# SCH_uCompute_Robot_2026-03-14.net
KiCad netlist of a schematic drawn in EasyEDA
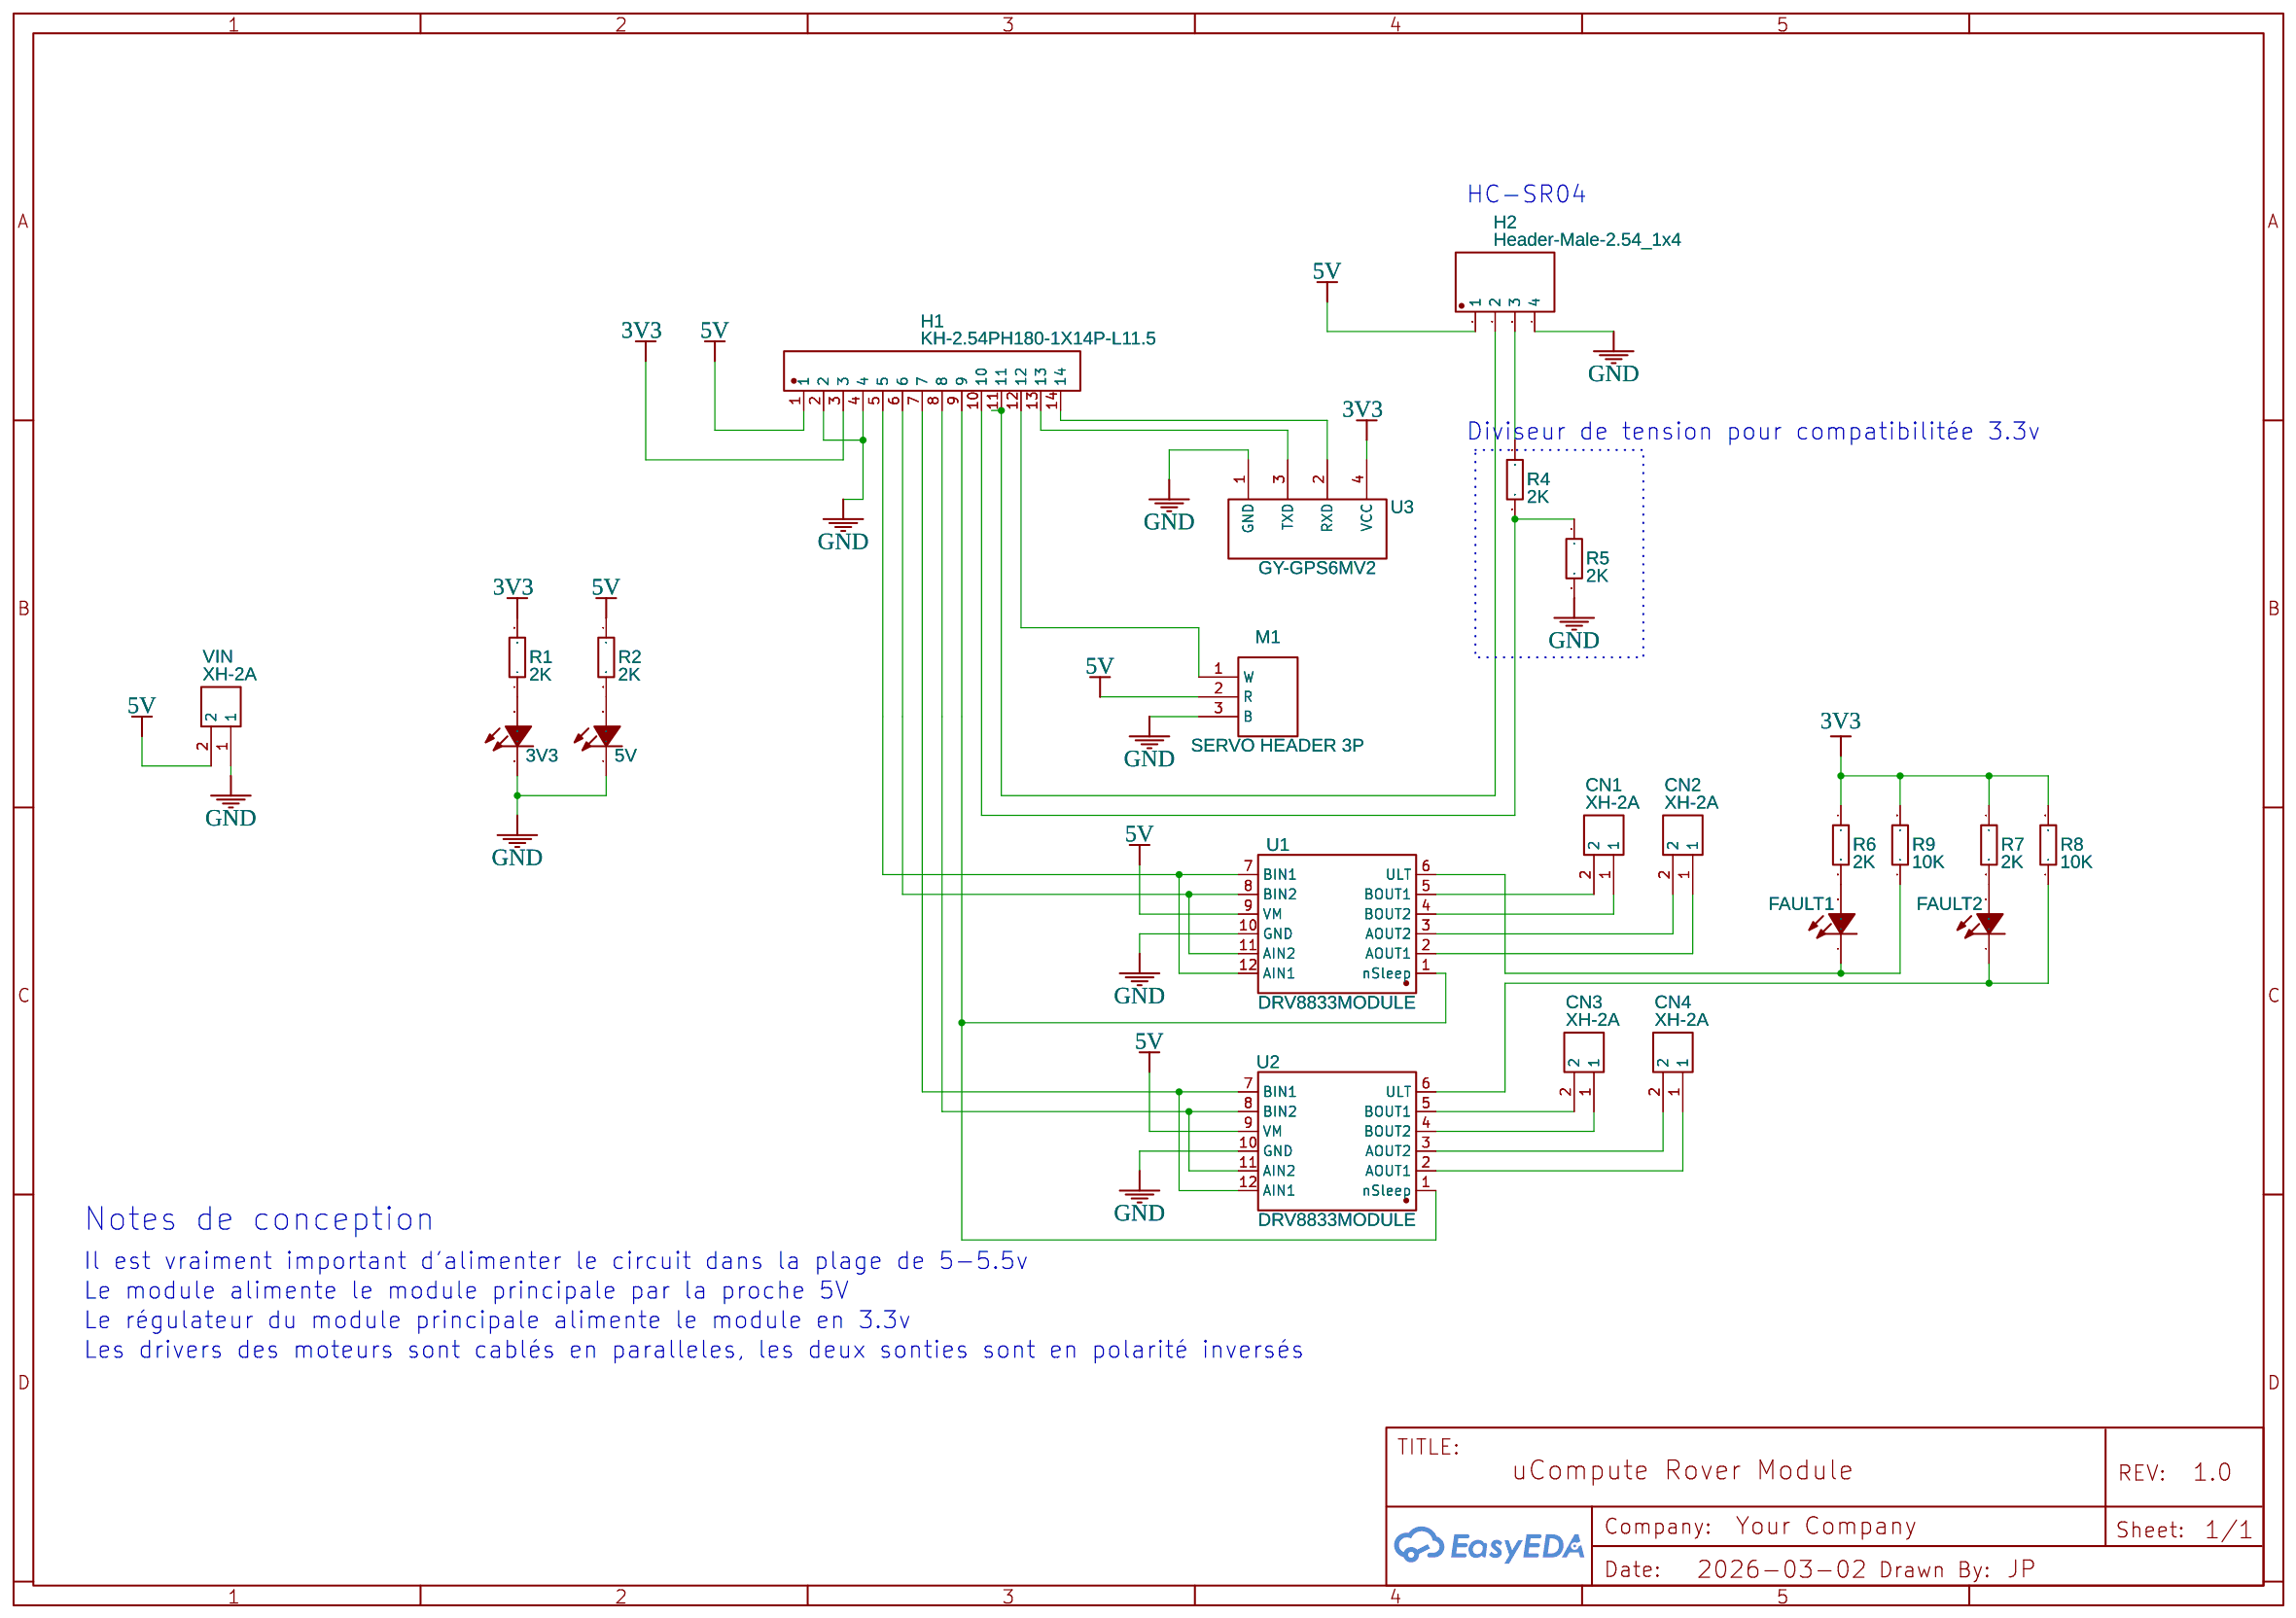
[diagram p0: schematic sheet]

(export (version "E")
  (design (tool "Eeschema 10.0.6"))
  (components
    (comp (ref "3V3")
      (value "XL-1206QPC")
      (fields (field (name "Manufacturer") "LCSC"))
      (libsource (lib "") (part "XL-1206QPC_1"))
    )
    (comp (ref "5V")
      (value "XL-1206QPC")
      (fields (field (name "Manufacturer") "LCSC"))
      (libsource (lib "") (part "XL-1206QPC_2"))
    )
    (comp (ref "CN1")
      (value "XH-2A")
      (fields (field (name "Manufacturer") "BOOMELE(博穆精密)"))
      (libsource (lib "") (part "XH-2A_1"))
    )
    (comp (ref "CN2")
      (value "XH-2A")
      (fields (field (name "Manufacturer") "BOOMELE(博穆精密)"))
      (libsource (lib "") (part "XH-2A_1"))
    )
    (comp (ref "CN3")
      (value "XH-2A")
      (fields (field (name "Manufacturer") "BOOMELE(博穆精密)"))
      (libsource (lib "") (part "XH-2A_1"))
    )
    (comp (ref "CN4")
      (value "XH-2A")
      (fields (field (name "Manufacturer") "BOOMELE(博穆精密)"))
      (libsource (lib "") (part "XH-2A_1"))
    )
    (comp (ref "FAULT1")
      (value "XL-1206QPC")
      (fields (field (name "Manufacturer") "LCSC"))
      (libsource (lib "") (part "XL-1206QPC"))
    )
    (comp (ref "FAULT2")
      (value "XL-1206QPC")
      (fields (field (name "Manufacturer") "LCSC"))
      (libsource (lib "") (part "XL-1206QPC"))
    )
    (comp (ref "H1")
      (value "KH-2.54PH180-1X14P-L11.5")
      (fields (field (name "Manufacturer") "kinghelm(金航标)"))
      (libsource (lib "") (part "KH-2.54PH180-1X14P-L11.5"))
    )
    (comp (ref "H2")
      (value "Header-Male-2.54_1x4")
      (fields (field (name "Manufacturer Part") "B-2100S04P-A110") (field (name "Manufacturer") "Ckmtw(灿科盟)"))
      (libsource (lib "") (part "Header-Male-2.54_1x4"))
    )
    (comp (ref "M1")
      (value "SERVO HEADER 3P")
      (fields (field (name "Manufacturer Part") "New SchematicLib"))
      (libsource (lib "") (part "SERVO HEADER 3P"))
    )
    (comp (ref "R1")
      (value "2K")
      (fields (field (name "Manufacturer Part") "RC0805DR-071KL") (field (name "Manufacturer") "YAGEO(国巨)"))
      (libsource (lib "") (part "RC0805DR-071KL_1"))
    )
    (comp (ref "R2")
      (value "2K")
      (fields (field (name "Manufacturer Part") "RC0805DR-071KL") (field (name "Manufacturer") "YAGEO(国巨)"))
      (libsource (lib "") (part "RC0805DR-071KL"))
    )
    (comp (ref "R4")
      (value "2K")
      (fields (field (name "Manufacturer Part") "RC0805DR-071KL") (field (name "Manufacturer") "YAGEO(国巨)"))
      (libsource (lib "") (part "RC0805DR-071KL"))
    )
    (comp (ref "R5")
      (value "2K")
      (fields (field (name "Manufacturer Part") "RC0805DR-071KL") (field (name "Manufacturer") "YAGEO(国巨)"))
      (libsource (lib "") (part "RC0805DR-071KL"))
    )
    (comp (ref "R6")
      (value "2K")
      (fields (field (name "Manufacturer Part") "RC0805DR-071KL") (field (name "Manufacturer") "YAGEO(国巨)"))
      (libsource (lib "") (part "RC0805DR-071KL"))
    )
    (comp (ref "R7")
      (value "2K")
      (fields (field (name "Manufacturer Part") "RC0805DR-071KL") (field (name "Manufacturer") "YAGEO(国巨)"))
      (libsource (lib "") (part "RC0805DR-071KL"))
    )
    (comp (ref "R8")
      (value "10K")
      (fields (field (name "Manufacturer Part") "RC0805DR-071KL") (field (name "Manufacturer") "YAGEO(国巨)"))
      (libsource (lib "") (part "RC0805DR-071KL_1"))
    )
    (comp (ref "R9")
      (value "10K")
      (fields (field (name "Manufacturer Part") "RC0805DR-071KL") (field (name "Manufacturer") "YAGEO(国巨)"))
      (libsource (lib "") (part "RC0805DR-071KL_1"))
    )
    (comp (ref "U1")
      (value "DRV8833MODULE")
      (fields (field (name "Manufacturer Part") "DRV8833PWR") (field (name "Manufacturer") "TI(德州仪器)"))
      (libsource (lib "") (part "DRV8833MODULE"))
    )
    (comp (ref "U2")
      (value "DRV8833MODULE")
      (fields (field (name "Manufacturer Part") "DRV8833PWR") (field (name "Manufacturer") "TI(德州仪器)"))
      (libsource (lib "") (part "DRV8833MODULE"))
    )
    (comp (ref "U3") (value "GY-GPS6MV2") (libsource (lib "") (part "GY-GPS6MV2")))
    (comp (ref "VIN")
      (value "XH-2A")
      (fields (field (name "Manufacturer") "BOOMELE(博穆精密)"))
      (libsource (lib "") (part "XH-2A"))
    )
  )
  (nets
    (net (code "1") (name "3V3") (class "Default")
      (node (ref "H1") (pin "3") (pinfunction "3_3") (pintype "unspecified"))
      (node (ref "R1") (pin "2") (pinfunction "2_2") (pintype "unspecified"))
      (node (ref "R6") (pin "1") (pinfunction "1_1") (pintype "unspecified"))
      (node (ref "R7") (pin "1") (pinfunction "1_1") (pintype "unspecified"))
      (node (ref "R8") (pin "2") (pinfunction "2_2") (pintype "unspecified"))
      (node (ref "R9") (pin "2") (pinfunction "2_2") (pintype "unspecified"))
      (node (ref "U3") (pin "4") (pinfunction "VCC_4") (pintype "bidirectional"))
    )
    (net (code "2") (name "5V") (class "Default")
      (node (ref "H1") (pin "1") (pinfunction "1_1") (pintype "unspecified"))
      (node (ref "H2") (pin "1") (pinfunction "1_1") (pintype "unspecified"))
      (node (ref "M1") (pin "2") (pinfunction "R_2") (pintype "unspecified"))
      (node (ref "R2") (pin "1") (pinfunction "1_1") (pintype "unspecified"))
      (node (ref "U1") (pin "9") (pinfunction "VM_9") (pintype "unspecified"))
      (node (ref "U2") (pin "9") (pinfunction "VM_9") (pintype "unspecified"))
      (node (ref "VIN") (pin "2") (pinfunction "2_2") (pintype "unspecified"))
    )
    (net (code "3") (name "GND") (class "Default")
      (node (ref "3V3") (pin "1") (pinfunction "K_1") (pintype "unspecified"))
      (node (ref "5V") (pin "1") (pinfunction "K_1") (pintype "unspecified"))
      (node (ref "H1") (pin "2") (pinfunction "2_2") (pintype "unspecified"))
      (node (ref "H1") (pin "4") (pinfunction "4_4") (pintype "unspecified"))
      (node (ref "H2") (pin "4") (pinfunction "4_4") (pintype "unspecified"))
      (node (ref "M1") (pin "3") (pinfunction "B_3") (pintype "unspecified"))
      (node (ref "R5") (pin "2") (pinfunction "2_2") (pintype "unspecified"))
      (node (ref "U1") (pin "10") (pinfunction "GND_10") (pintype "unspecified"))
      (node (ref "U2") (pin "10") (pinfunction "GND_10") (pintype "unspecified"))
      (node (ref "U3") (pin "1") (pinfunction "GND_1") (pintype "bidirectional"))
      (node (ref "VIN") (pin "1") (pinfunction "1_1") (pintype "unspecified"))
    )
    (net (code "4") (name "Net-(3V3-A)") (class "Default")
      (node (ref "3V3") (pin "2") (pinfunction "A_2") (pintype "unspecified"))
      (node (ref "R1") (pin "1") (pinfunction "1_1") (pintype "unspecified"))
    )
    (net (code "5") (name "Net-(5V-A)") (class "Default")
      (node (ref "5V") (pin "2") (pinfunction "A_2") (pintype "unspecified"))
      (node (ref "R2") (pin "2") (pinfunction "2_2") (pintype "unspecified"))
    )
    (net (code "6") (name "Net-(FAULT1-A)") (class "Default")
      (node (ref "FAULT1") (pin "2") (pinfunction "A_2") (pintype "unspecified"))
      (node (ref "R6") (pin "2") (pinfunction "2_2") (pintype "unspecified"))
    )
    (net (code "7") (name "Net-(FAULT1-K)") (class "Default")
      (node (ref "FAULT1") (pin "1") (pinfunction "K_1") (pintype "unspecified"))
      (node (ref "R9") (pin "1") (pinfunction "1_1") (pintype "unspecified"))
      (node (ref "U1") (pin "6") (pinfunction "ULT_6") (pintype "unspecified"))
    )
    (net (code "8") (name "Net-(FAULT2-A)") (class "Default")
      (node (ref "FAULT2") (pin "2") (pinfunction "A_2") (pintype "unspecified"))
      (node (ref "R7") (pin "2") (pinfunction "2_2") (pintype "unspecified"))
    )
    (net (code "9") (name "Net-(FAULT2-K)") (class "Default")
      (node (ref "FAULT2") (pin "1") (pinfunction "K_1") (pintype "unspecified"))
      (node (ref "R8") (pin "1") (pinfunction "1_1") (pintype "unspecified"))
      (node (ref "U2") (pin "6") (pinfunction "ULT_6") (pintype "unspecified"))
    )
    (net (code "10") (name "Net-(H1-Pad10)") (class "Default")
      (node (ref "H1") (pin "10") (pinfunction "10_10") (pintype "unspecified"))
      (node (ref "R4") (pin "2") (pinfunction "2_2") (pintype "unspecified"))
      (node (ref "R5") (pin "1") (pinfunction "1_1") (pintype "unspecified"))
    )
    (net (code "11") (name "Net-(H1-Pad11)") (class "Default")
      (node (ref "H1") (pin "11") (pinfunction "11_11") (pintype "unspecified"))
      (node (ref "H2") (pin "2") (pinfunction "2_2") (pintype "unspecified"))
    )
    (net (code "12") (name "Net-(H2-Pad3)") (class "Default")
      (node (ref "H2") (pin "3") (pinfunction "3_3") (pintype "unspecified"))
      (node (ref "R4") (pin "1") (pinfunction "1_1") (pintype "unspecified"))
    )
    (net (code "13") (name "Net-(M1-W)") (class "Default")
      (node (ref "H1") (pin "12") (pinfunction "12_12") (pintype "unspecified"))
      (node (ref "M1") (pin "1") (pinfunction "W_1") (pintype "unspecified"))
    )
    (net (code "14") (name "Net-(U1-AIN1)") (class "Default")
      (node (ref "H1") (pin "5") (pinfunction "5_5") (pintype "unspecified"))
      (node (ref "U1") (pin "12") (pinfunction "AIN1_12") (pintype "unspecified"))
      (node (ref "U1") (pin "7") (pinfunction "BIN1_7") (pintype "unspecified"))
    )
    (net (code "15") (name "Net-(U1-AIN2)") (class "Default")
      (node (ref "H1") (pin "6") (pinfunction "6_6") (pintype "unspecified"))
      (node (ref "U1") (pin "11") (pinfunction "AIN2_11") (pintype "unspecified"))
      (node (ref "U1") (pin "8") (pinfunction "BIN2_8") (pintype "unspecified"))
    )
    (net (code "16") (name "Net-(U1-AOUT1)") (class "Default")
      (node (ref "CN2") (pin "1") (pinfunction "1_1") (pintype "unspecified"))
      (node (ref "U1") (pin "2") (pinfunction "AOUT1_2") (pintype "unspecified"))
    )
    (net (code "17") (name "Net-(U1-AOUT2)") (class "Default")
      (node (ref "CN2") (pin "2") (pinfunction "2_2") (pintype "unspecified"))
      (node (ref "U1") (pin "3") (pinfunction "AOUT2_3") (pintype "unspecified"))
    )
    (net (code "18") (name "Net-(U1-BOUT1)") (class "Default")
      (node (ref "CN1") (pin "2") (pinfunction "2_2") (pintype "unspecified"))
      (node (ref "U1") (pin "5") (pinfunction "BOUT1_5") (pintype "unspecified"))
    )
    (net (code "19") (name "Net-(U1-BOUT2)") (class "Default")
      (node (ref "CN1") (pin "1") (pinfunction "1_1") (pintype "unspecified"))
      (node (ref "U1") (pin "4") (pinfunction "BOUT2_4") (pintype "unspecified"))
    )
    (net (code "20") (name "Net-(U1-nSleep)") (class "Default")
      (node (ref "H1") (pin "9") (pinfunction "9_9") (pintype "unspecified"))
      (node (ref "U1") (pin "1") (pinfunction "nSleep_1") (pintype "unspecified"))
      (node (ref "U2") (pin "1") (pinfunction "nSleep_1") (pintype "unspecified"))
    )
    (net (code "21") (name "Net-(U2-AIN1)") (class "Default")
      (node (ref "H1") (pin "7") (pinfunction "7_7") (pintype "unspecified"))
      (node (ref "U2") (pin "12") (pinfunction "AIN1_12") (pintype "unspecified"))
      (node (ref "U2") (pin "7") (pinfunction "BIN1_7") (pintype "unspecified"))
    )
    (net (code "22") (name "Net-(U2-AIN2)") (class "Default")
      (node (ref "H1") (pin "8") (pinfunction "8_8") (pintype "unspecified"))
      (node (ref "U2") (pin "11") (pinfunction "AIN2_11") (pintype "unspecified"))
      (node (ref "U2") (pin "8") (pinfunction "BIN2_8") (pintype "unspecified"))
    )
    (net (code "23") (name "Net-(U2-AOUT1)") (class "Default")
      (node (ref "CN4") (pin "1") (pinfunction "1_1") (pintype "unspecified"))
      (node (ref "U2") (pin "2") (pinfunction "AOUT1_2") (pintype "unspecified"))
    )
    (net (code "24") (name "Net-(U2-AOUT2)") (class "Default")
      (node (ref "CN4") (pin "2") (pinfunction "2_2") (pintype "unspecified"))
      (node (ref "U2") (pin "3") (pinfunction "AOUT2_3") (pintype "unspecified"))
    )
    (net (code "25") (name "Net-(U2-BOUT1)") (class "Default")
      (node (ref "CN3") (pin "2") (pinfunction "2_2") (pintype "unspecified"))
      (node (ref "U2") (pin "5") (pinfunction "BOUT1_5") (pintype "unspecified"))
    )
    (net (code "26") (name "Net-(U2-BOUT2)") (class "Default")
      (node (ref "CN3") (pin "1") (pinfunction "1_1") (pintype "unspecified"))
      (node (ref "U2") (pin "4") (pinfunction "BOUT2_4") (pintype "unspecified"))
    )
    (net (code "27") (name "Net-(U3-RXD)") (class "Default")
      (node (ref "H1") (pin "14") (pinfunction "14_14") (pintype "unspecified"))
      (node (ref "U3") (pin "2") (pinfunction "RXD_2") (pintype "bidirectional"))
    )
    (net (code "28") (name "Net-(U3-TXD)") (class "Default")
      (node (ref "H1") (pin "13") (pinfunction "13_13") (pintype "unspecified"))
      (node (ref "U3") (pin "3") (pinfunction "TXD_3") (pintype "bidirectional"))
    )
  )
)
